# sheet_reciver.net
KiCad netlist of a schematic drawn in Altium Designer
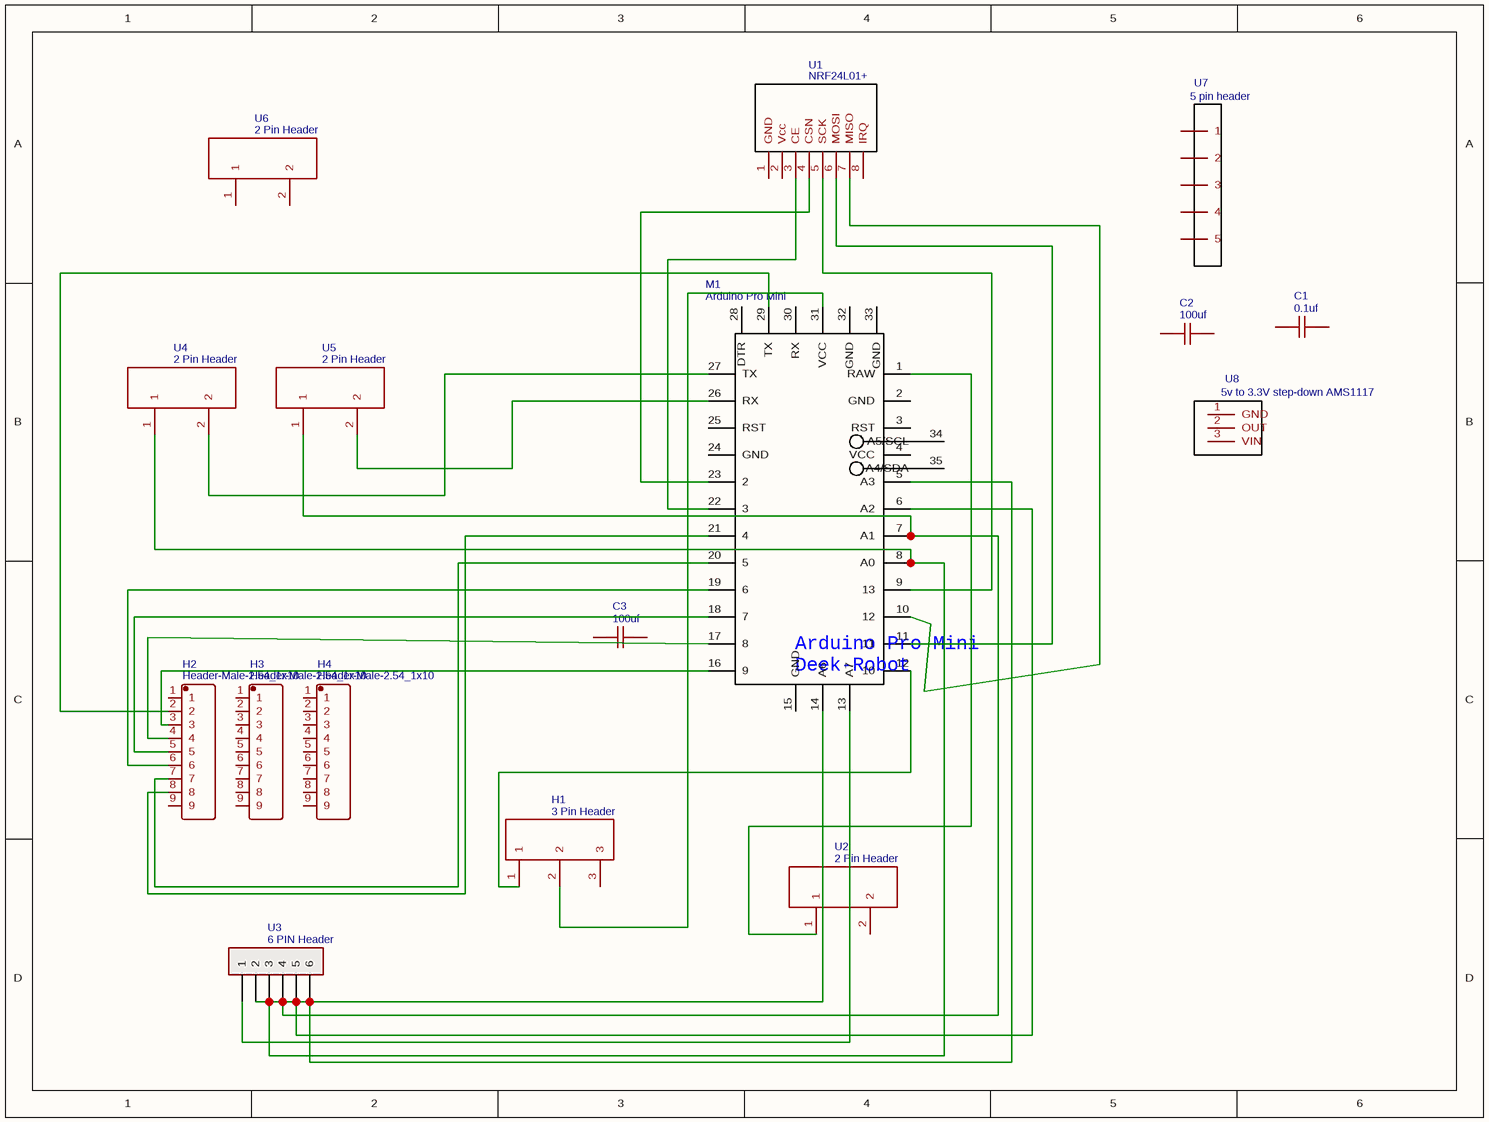
[diagram p0: sheet reciver.schdoc]

(export (version "E")
  (design (tool "Eeschema 10.0.6"))
  (components
    (comp (ref "C1")
      (value "0.1uf")
      (fields (field (name "CONTRIBUTOR") "LCEDA_Lib"))
      (libsource (lib "altium-import") (part "root_0_0.1uf_"))
    )
    (comp (ref "C2")
      (value "100uf")
      (fields (field (name "CONTRIBUTOR") "LCEDA_Lib"))
      (libsource (lib "altium-import") (part "root_0_100uf_"))
    )
    (comp (ref "C3")
      (value "100uf")
      (fields (field (name "CONTRIBUTOR") "LCEDA_Lib"))
      (libsource (lib "altium-import") (part "root_0_100uf_"))
    )
    (comp (ref "H1")
      (value "3 Pin Header")
      (fields (field (name "CONTRIBUTOR") "18635746"))
      (libsource (lib "altium-import") (part "root_0_3 Pin Header_"))
    )
    (comp (ref "H2")
      (value "Header-Male-2.54_1x10")
      (fields
        (field (name "BOM_MANUFACTURER PART") "Headers  Pins2.54mm1*9p 9 pins")
        (field (name "BOM_SUPPLIER PART") "C57369")
        (field (name "CONTRIBUTOR") "1rahul.thakur")
      )
      (libsource (lib "altium-import") (part "root_0_Header-Male-2.54_1x10_"))
    )
    (comp (ref "H3")
      (value "Header-Male-2.54_1x10")
      (fields
        (field (name "BOM_MANUFACTURER PART") "Headers  Pins2.54mm1*9p 9 pins")
        (field (name "BOM_SUPPLIER PART") "C57369")
        (field (name "CONTRIBUTOR") "1rahul.thakur")
      )
      (libsource (lib "altium-import") (part "root_0_Header-Male-2.54_1x10_"))
    )
    (comp (ref "H4")
      (value "Header-Male-2.54_1x10")
      (fields
        (field (name "BOM_MANUFACTURER PART") "Headers  Pins2.54mm1*9p 9 pins")
        (field (name "BOM_SUPPLIER PART") "C57369")
        (field (name "CONTRIBUTOR") "1rahul.thakur")
      )
      (libsource (lib "altium-import") (part "root_0_Header-Male-2.54_1x10_"))
    )
    (comp (ref "M1")
      (value "Arduino Pro Mini")
      (fields (field (name "CONTRIBUTOR") "albertal"))
      (libsource (lib "altium-import") (part "root_0_Arduino Pro Mini_"))
    )
    (comp (ref "U1")
      (value "NRF24L01+")
      (fields (field (name "CONTRIBUTOR") "Sinuhe Pardo"))
      (libsource (lib "altium-import") (part "root_1_NRF24L01+_"))
    )
    (comp (ref "U2")
      (value "2 Pin Header")
      (fields (field (name "CONTRIBUTOR") "18635746"))
      (libsource (lib "altium-import") (part "root_0_2 Pin Header_"))
    )
    (comp (ref "U3")
      (value "6 PIN Header")
      (fields
        (field (name "BOM_MANUFACTURER PART") "New SchematicLib")
        (field (name "CONTRIBUTOR") "Bartosz Koziel")
      )
      (libsource (lib "altium-import") (part "root_1_6 PIN Header_"))
    )
    (comp (ref "U4")
      (value "2 Pin Header")
      (fields (field (name "CONTRIBUTOR") "18635746"))
      (libsource (lib "altium-import") (part "root_0_2 Pin Header_"))
    )
    (comp (ref "U5")
      (value "2 Pin Header")
      (fields (field (name "CONTRIBUTOR") "18635746"))
      (libsource (lib "altium-import") (part "root_0_2 Pin Header_"))
    )
    (comp (ref "U6")
      (value "2 Pin Header")
      (fields (field (name "CONTRIBUTOR") "18635746"))
      (libsource (lib "altium-import") (part "root_0_2 Pin Header_"))
    )
    (comp (ref "U7")
      (value "5 pin header")
      (fields (field (name "CONTRIBUTOR") "alberto.perez.madruga"))
      (libsource (lib "altium-import") (part "root_0_5 pin header_"))
    )
    (comp (ref "U8")
      (value "5v to 3.3V step-down AMS1117")
      (fields (field (name "CONTRIBUTOR") "winter2015"))
      (libsource (lib "altium-import") (part "root_0_5v to 3.3V step-down AMS1117_"))
    )
  )
  (nets
    (net (code "1") (name "Net-(H1-Pad2)") (class "Default")
      (node (ref "H1") (pin "2") (pinfunction "2_2") (pintype "passive"))
      (node (ref "M1") (pin "31") (pinfunction "VCC_31") (pintype "passive"))
    )
    (net (code "2") (name "Net-(H2-Pad2)") (class "Default")
      (node (ref "H2") (pin "2") (pinfunction "2_2") (pintype "passive"))
      (node (ref "M1") (pin "29") (pinfunction "TX_29") (pintype "passive"))
    )
    (net (code "3") (name "Net-(M1-2)") (class "Default")
      (node (ref "M1") (pin "23") (pinfunction "2_23") (pintype "passive"))
      (node (ref "U1") (pin "4") (pinfunction "CSN_4") (pintype "passive"))
    )
    (net (code "4") (name "Net-(M1-3)") (class "Default")
      (node (ref "M1") (pin "22") (pinfunction "3_22") (pintype "passive"))
      (node (ref "U1") (pin "3") (pinfunction "CE_3") (pintype "passive"))
    )
    (net (code "5") (name "Net-(M1-4)") (class "Default")
      (node (ref "H2") (pin "8") (pinfunction "8_8") (pintype "passive"))
      (node (ref "M1") (pin "21") (pinfunction "4_21") (pintype "passive"))
    )
    (net (code "6") (name "Net-(M1-5)") (class "Default")
      (node (ref "H2") (pin "7") (pinfunction "7_7") (pintype "passive"))
      (node (ref "M1") (pin "20") (pinfunction "5_20") (pintype "passive"))
    )
    (net (code "7") (name "Net-(M1-6)") (class "Default")
      (node (ref "H2") (pin "6") (pinfunction "6_6") (pintype "passive"))
      (node (ref "M1") (pin "19") (pinfunction "6_19") (pintype "passive"))
    )
    (net (code "8") (name "Net-(M1-7)") (class "Default")
      (node (ref "H2") (pin "5") (pinfunction "5_5") (pintype "passive"))
      (node (ref "M1") (pin "18") (pinfunction "7_18") (pintype "passive"))
    )
    (net (code "9") (name "Net-(M1-8)") (class "Default")
      (node (ref "H2") (pin "4") (pinfunction "4_4") (pintype "passive"))
      (node (ref "M1") (pin "17") (pinfunction "8_17") (pintype "passive"))
    )
    (net (code "10") (name "Net-(M1-9)") (class "Default")
      (node (ref "H2") (pin "3") (pinfunction "3_3") (pintype "passive"))
      (node (ref "M1") (pin "16") (pinfunction "9_16") (pintype "passive"))
    )
    (net (code "11") (name "Net-(M1-10)") (class "Default")
      (node (ref "H1") (pin "1") (pinfunction "1_1") (pintype "passive"))
      (node (ref "M1") (pin "12") (pinfunction "10_12") (pintype "passive"))
    )
    (net (code "12") (name "Net-(M1-12)") (class "Default")
      (node (ref "M1") (pin "10") (pinfunction "12_10") (pintype "passive"))
      (node (ref "U1") (pin "7") (pinfunction "MISO_7") (pintype "passive"))
    )
    (net (code "13") (name "Net-(M1-13)") (class "Default")
      (node (ref "M1") (pin "9") (pinfunction "13_9") (pintype "passive"))
      (node (ref "U1") (pin "5") (pinfunction "SCK_5") (pintype "passive"))
    )
    (net (code "14") (name "Net-(M1-A0)") (class "Default")
      (node (ref "M1") (pin "14") (pinfunction "A6_14") (pintype "passive"))
      (node (ref "M1") (pin "5") (pinfunction "A3_5") (pintype "passive"))
      (node (ref "M1") (pin "6") (pinfunction "A2_6") (pintype "passive"))
      (node (ref "M1") (pin "7") (pinfunction "A1_7") (pintype "passive"))
      (node (ref "M1") (pin "8") (pinfunction "A0_8") (pintype "passive"))
      (node (ref "U3") (pin "2") (pinfunction "2_2") (pintype "passive"))
      (node (ref "U3") (pin "3") (pinfunction "3_3") (pintype "passive"))
      (node (ref "U3") (pin "4") (pinfunction "4_4") (pintype "passive"))
      (node (ref "U3") (pin "5") (pinfunction "5_5") (pintype "passive"))
      (node (ref "U3") (pin "6") (pinfunction "6_6") (pintype "passive"))
      (node (ref "U4") (pin "1") (pinfunction "1_1") (pintype "passive"))
      (node (ref "U5") (pin "1") (pinfunction "1_1") (pintype "passive"))
    )
    (net (code "15") (name "Net-(M1-A7)") (class "Default")
      (node (ref "M1") (pin "13") (pinfunction "A7_13") (pintype "passive"))
      (node (ref "U3") (pin "1") (pinfunction "1_1") (pintype "passive"))
    )
    (net (code "16") (name "Net-(M1-RAW)") (class "Default")
      (node (ref "M1") (pin "1") (pinfunction "RAW_1") (pintype "passive"))
      (node (ref "U2") (pin "1") (pinfunction "1_1") (pintype "passive"))
    )
    (net (code "17") (name "Net-(M1-RX-Pad26)") (class "Default")
      (node (ref "M1") (pin "26") (pinfunction "RX_26") (pintype "passive"))
      (node (ref "U5") (pin "2") (pinfunction "2_2") (pintype "passive"))
    )
    (net (code "18") (name "Net-(M1-TX-Pad27)") (class "Default")
      (node (ref "M1") (pin "27") (pinfunction "TX_27") (pintype "passive"))
      (node (ref "U4") (pin "2") (pinfunction "2_2") (pintype "passive"))
    )
    (net (code "19") (name "Net-(U1-MOSI)") (class "Default")
      (node (ref "M1") (pin "11") (pinfunction "11_11") (pintype "passive"))
      (node (ref "U1") (pin "6") (pinfunction "MOSI_6") (pintype "passive"))
    )
    (net (code "20") (name "unconnected-(C1-Pad1)") (class "Default")
      (node (ref "C1") (pin "1") (pinfunction "1_1") (pintype "passive"))
    )
    (net (code "21") (name "unconnected-(C1-Pad2)") (class "Default")
      (node (ref "C1") (pin "2") (pinfunction "2_2") (pintype "passive"))
    )
    (net (code "22") (name "unconnected-(C2-Pad1)") (class "Default")
      (node (ref "C2") (pin "1") (pinfunction "1_1") (pintype "passive"))
    )
    (net (code "23") (name "unconnected-(C2-Pad2)") (class "Default")
      (node (ref "C2") (pin "2") (pinfunction "2_2") (pintype "passive"))
    )
    (net (code "24") (name "unconnected-(C3-Pad1)") (class "Default")
      (node (ref "C3") (pin "1") (pinfunction "1_1") (pintype "passive"))
    )
    (net (code "25") (name "unconnected-(C3-Pad2)") (class "Default")
      (node (ref "C3") (pin "2") (pinfunction "2_2") (pintype "passive"))
    )
    (net (code "26") (name "unconnected-(H1-Pad3)") (class "Default")
      (node (ref "H1") (pin "3") (pinfunction "3_3") (pintype "passive"))
    )
    (net (code "27") (name "unconnected-(H2-Pad1)") (class "Default")
      (node (ref "H2") (pin "1") (pinfunction "1_1") (pintype "passive"))
    )
    (net (code "28") (name "unconnected-(H2-Pad9)") (class "Default")
      (node (ref "H2") (pin "9") (pinfunction "9_9") (pintype "passive"))
    )
    (net (code "29") (name "unconnected-(H3-Pad1)") (class "Default")
      (node (ref "H3") (pin "1") (pinfunction "1_1") (pintype "passive"))
    )
    (net (code "30") (name "unconnected-(H3-Pad2)") (class "Default")
      (node (ref "H3") (pin "2") (pinfunction "2_2") (pintype "passive"))
    )
    (net (code "31") (name "unconnected-(H3-Pad3)") (class "Default")
      (node (ref "H3") (pin "3") (pinfunction "3_3") (pintype "passive"))
    )
    (net (code "32") (name "unconnected-(H3-Pad4)") (class "Default")
      (node (ref "H3") (pin "4") (pinfunction "4_4") (pintype "passive"))
    )
    (net (code "33") (name "unconnected-(H3-Pad5)") (class "Default")
      (node (ref "H3") (pin "5") (pinfunction "5_5") (pintype "passive"))
    )
    (net (code "34") (name "unconnected-(H3-Pad6)") (class "Default")
      (node (ref "H3") (pin "6") (pinfunction "6_6") (pintype "passive"))
    )
    (net (code "35") (name "unconnected-(H3-Pad7)") (class "Default")
      (node (ref "H3") (pin "7") (pinfunction "7_7") (pintype "passive"))
    )
    (net (code "36") (name "unconnected-(H3-Pad8)") (class "Default")
      (node (ref "H3") (pin "8") (pinfunction "8_8") (pintype "passive"))
    )
    (net (code "37") (name "unconnected-(H3-Pad9)") (class "Default")
      (node (ref "H3") (pin "9") (pinfunction "9_9") (pintype "passive"))
    )
    (net (code "38") (name "unconnected-(H4-Pad1)") (class "Default")
      (node (ref "H4") (pin "1") (pinfunction "1_1") (pintype "passive"))
    )
    (net (code "39") (name "unconnected-(H4-Pad2)") (class "Default")
      (node (ref "H4") (pin "2") (pinfunction "2_2") (pintype "passive"))
    )
    (net (code "40") (name "unconnected-(H4-Pad3)") (class "Default")
      (node (ref "H4") (pin "3") (pinfunction "3_3") (pintype "passive"))
    )
    (net (code "41") (name "unconnected-(H4-Pad4)") (class "Default")
      (node (ref "H4") (pin "4") (pinfunction "4_4") (pintype "passive"))
    )
    (net (code "42") (name "unconnected-(H4-Pad5)") (class "Default")
      (node (ref "H4") (pin "5") (pinfunction "5_5") (pintype "passive"))
    )
    (net (code "43") (name "unconnected-(H4-Pad6)") (class "Default")
      (node (ref "H4") (pin "6") (pinfunction "6_6") (pintype "passive"))
    )
    (net (code "44") (name "unconnected-(H4-Pad7)") (class "Default")
      (node (ref "H4") (pin "7") (pinfunction "7_7") (pintype "passive"))
    )
    (net (code "45") (name "unconnected-(H4-Pad8)") (class "Default")
      (node (ref "H4") (pin "8") (pinfunction "8_8") (pintype "passive"))
    )
    (net (code "46") (name "unconnected-(H4-Pad9)") (class "Default")
      (node (ref "H4") (pin "9") (pinfunction "9_9") (pintype "passive"))
    )
    (net (code "47") (name "unconnected-(M1-A4{slash}SDA-Pad35)") (class "Default")
      (node (ref "M1") (pin "35") (pinfunction "A4/SDA_35") (pintype "passive"))
    )
    (net (code "48") (name "unconnected-(M1-A5{slash}SCL-Pad34)") (class "Default")
      (node (ref "M1") (pin "34") (pinfunction "A5/SCL_34") (pintype "passive"))
    )
    (net (code "49") (name "unconnected-(M1-DTR-Pad28)") (class "Default")
      (node (ref "M1") (pin "28") (pinfunction "DTR_28") (pintype "passive"))
    )
    (net (code "50") (name "unconnected-(M1-GND-Pad2)") (class "Default")
      (node (ref "M1") (pin "2") (pinfunction "GND_2") (pintype "passive"))
    )
    (net (code "51") (name "unconnected-(M1-GND-Pad15)") (class "Default")
      (node (ref "M1") (pin "15") (pinfunction "GND_15") (pintype "passive"))
    )
    (net (code "52") (name "unconnected-(M1-GND-Pad24)") (class "Default")
      (node (ref "M1") (pin "24") (pinfunction "GND_24") (pintype "passive"))
    )
    (net (code "53") (name "unconnected-(M1-GND-Pad32)") (class "Default")
      (node (ref "M1") (pin "32") (pinfunction "GND_32") (pintype "passive"))
    )
    (net (code "54") (name "unconnected-(M1-GND-Pad33)") (class "Default")
      (node (ref "M1") (pin "33") (pinfunction "GND_33") (pintype "passive"))
    )
    (net (code "55") (name "unconnected-(M1-RST-Pad3)") (class "Default")
      (node (ref "M1") (pin "3") (pinfunction "RST_3") (pintype "passive"))
    )
    (net (code "56") (name "unconnected-(M1-RST-Pad25)") (class "Default")
      (node (ref "M1") (pin "25") (pinfunction "RST_25") (pintype "passive"))
    )
    (net (code "57") (name "unconnected-(M1-RX-Pad30)") (class "Default")
      (node (ref "M1") (pin "30") (pinfunction "RX_30") (pintype "passive"))
    )
    (net (code "58") (name "unconnected-(M1-VCC-Pad4)") (class "Default")
      (node (ref "M1") (pin "4") (pinfunction "VCC_4") (pintype "passive"))
    )
    (net (code "59") (name "unconnected-(U1-GND-Pad1)") (class "Default")
      (node (ref "U1") (pin "1") (pinfunction "GND_1") (pintype "passive"))
    )
    (net (code "60") (name "unconnected-(U1-IRQ-Pad8)") (class "Default")
      (node (ref "U1") (pin "8") (pinfunction "IRQ_8") (pintype "passive"))
    )
    (net (code "61") (name "unconnected-(U1-Vcc-Pad2)") (class "Default")
      (node (ref "U1") (pin "2") (pinfunction "Vcc_2") (pintype "passive"))
    )
    (net (code "62") (name "unconnected-(U2-Pad2)") (class "Default")
      (node (ref "U2") (pin "2") (pinfunction "2_2") (pintype "passive"))
    )
    (net (code "63") (name "unconnected-(U6-Pad1)") (class "Default")
      (node (ref "U6") (pin "1") (pinfunction "1_1") (pintype "passive"))
    )
    (net (code "64") (name "unconnected-(U6-Pad2)") (class "Default")
      (node (ref "U6") (pin "2") (pinfunction "2_2") (pintype "passive"))
    )
    (net (code "65") (name "unconnected-(U7-Pad1)") (class "Default")
      (node (ref "U7") (pin "1") (pinfunction "1_1") (pintype "passive"))
    )
    (net (code "66") (name "unconnected-(U7-Pad2)") (class "Default")
      (node (ref "U7") (pin "2") (pinfunction "2_2") (pintype "passive"))
    )
    (net (code "67") (name "unconnected-(U7-Pad3)") (class "Default")
      (node (ref "U7") (pin "3") (pinfunction "3_3") (pintype "passive"))
    )
    (net (code "68") (name "unconnected-(U7-Pad4)") (class "Default")
      (node (ref "U7") (pin "4") (pinfunction "4_4") (pintype "passive"))
    )
    (net (code "69") (name "unconnected-(U7-Pad5)") (class "Default")
      (node (ref "U7") (pin "5") (pinfunction "5_5") (pintype "passive"))
    )
    (net (code "70") (name "unconnected-(U8-GND-Pad1)") (class "Default")
      (node (ref "U8") (pin "1") (pinfunction "GND_1") (pintype "passive"))
    )
    (net (code "71") (name "unconnected-(U8-OUT-Pad2)") (class "Default")
      (node (ref "U8") (pin "2") (pinfunction "OUT_2") (pintype "passive"))
    )
    (net (code "72") (name "unconnected-(U8-VIN-Pad3)") (class "Default")
      (node (ref "U8") (pin "3") (pinfunction "VIN_3") (pintype "passive"))
    )
  )
)
